# Dental_Sensor.net
KiCad netlist of a schematic drawn in Altium Designer
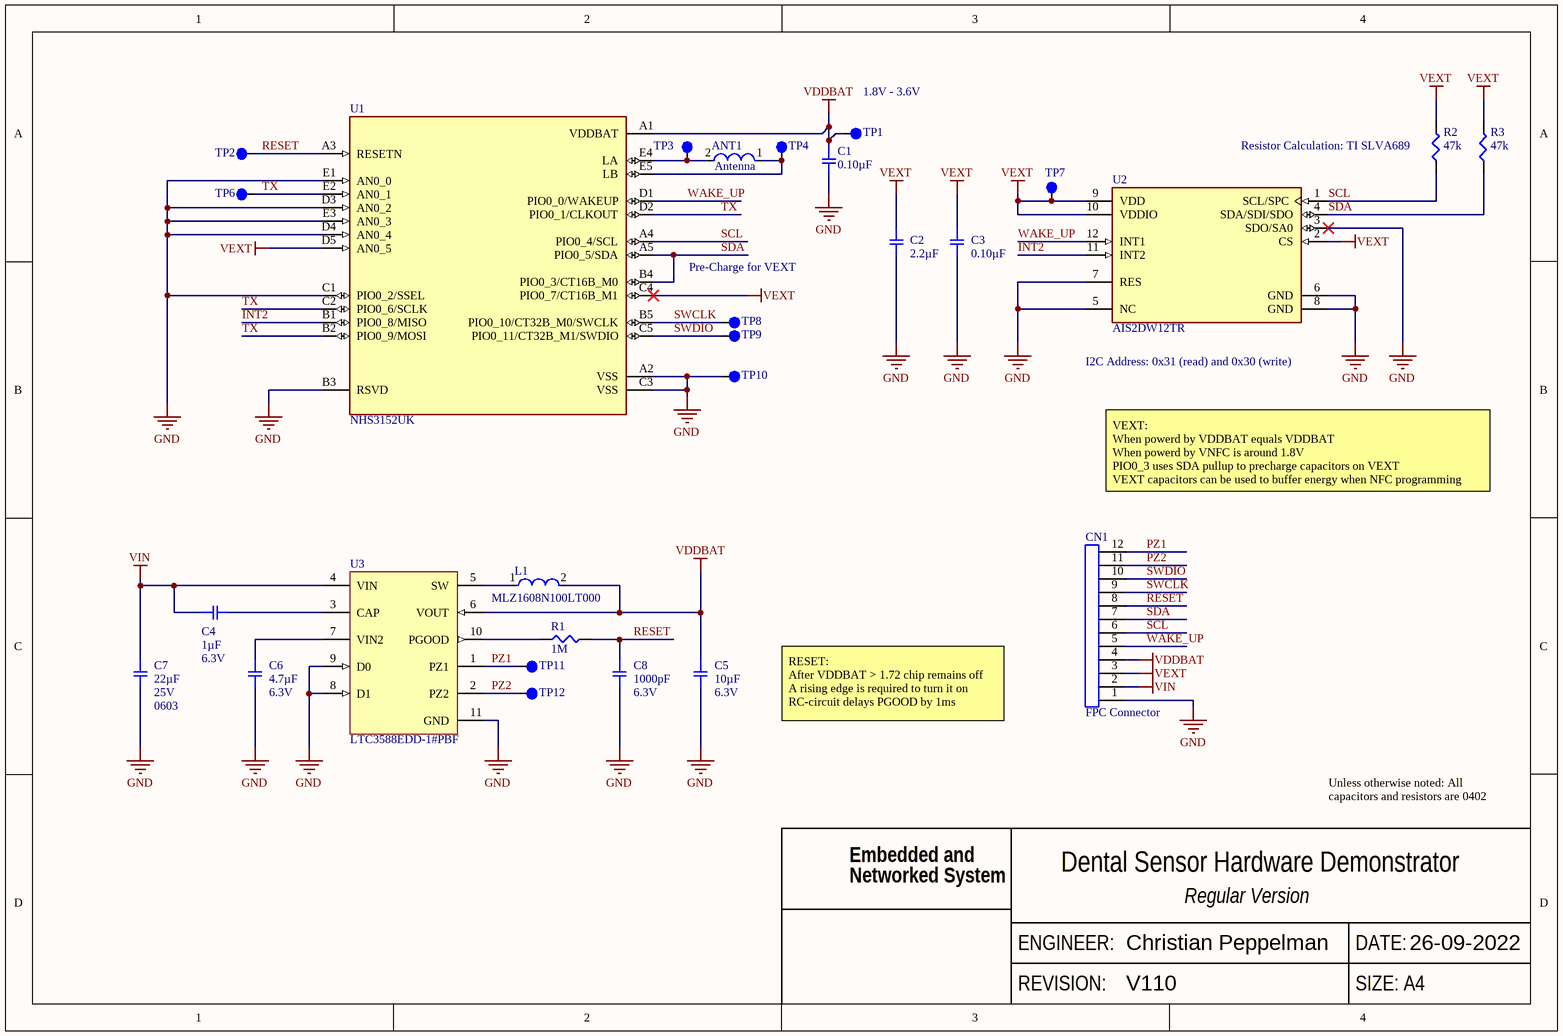
[diagram p0: Dental Sensor.SchDoc]

(export (version "E")
  (design (tool "Eeschema 10.0.6"))
  (components
    (comp (ref "ANT1")
      (value "Antenna")
      (footprint "NFC Antenna")
      (description "Track 0.2; Gap 0.1; Height 4.6; Width 14.5;")
      (libsource (lib "Library") (part "NFC Antenna"))
    )
    (comp (ref "C1")
      (value "0.10µF")
      (footprint "CAPC1005X03N")
      (description "CAP CER 0.1UF 6.3V X5R 0402")
      (fields
        (field (name "DIGI-KEY PART NUMBER") "490-6287-1-ND")
        (field (name "PART NUMBER") "GRM155R60J104KA01D")
      )
      (libsource (lib "capacitor_murata_0402") (part "GRM155R60J104KA01D"))
    )
    (comp (ref "C2")
      (value "2.2µF")
      (footprint "CAPC1005X03N")
      (description "CAP CER 2.2UF 6.3V X5R 0402")
      (fields
        (field (name "DIGI-KEY PART NUMBER") "490-12250-1-ND")
        (field (name "PART NUMBER") "GRT155R60J225KE01D")
      )
      (libsource (lib "capacitor_murata_0402") (part "GRT155R60J225KE01D"))
    )
    (comp (ref "C3")
      (value "0.10µF")
      (footprint "CAPC1005X03N")
      (description "CAP CER 0.1UF 6.3V X5R 0402")
      (fields
        (field (name "DIGI-KEY PART NUMBER") "490-6287-1-ND")
        (field (name "PART NUMBER") "GRM155R60J104KA01D")
      )
      (libsource (lib "capacitor_murata_0402") (part "GRM155R60J104KA01D"))
    )
    (comp (ref "C4")
      (value "1µF")
      (footprint "CAPC1005X03N")
      (description "CAP CER 1UF 6.3V X7R 0402")
      (fields
        (field (name "DIGI-KEY PART NUMBER") "490-9665-1-ND")
        (field (name "PART NUMBER") "GRM155R70J105MA12D")
        (field (name "VOLTAGE") "6.3V")
      )
      (libsource (lib "capacitor_murata_0402") (part "GRM155R70J105MA12D"))
    )
    (comp (ref "C5")
      (value "10µF")
      (footprint "CAPC1005X03N")
      (description "CAP CER 10UF 6.3V X5R 0402")
      (fields
        (field (name "DIGI-KEY PART NUMBER") "490-13811-1-ND")
        (field (name "PART NUMBER") "GRM155R60J106ME44D")
        (field (name "VOLTAGE") "6.3V")
      )
      (libsource (lib "capacitor_murata_0402") (part "GRM155R60J106ME44D"))
    )
    (comp (ref "C6")
      (value "4.7µF")
      (footprint "CAPC1005X03N")
      (description "CAP CER 4.7UF 6.3V X5R 0402")
      (fields
        (field (name "DIGI-KEY PART NUMBER") "490-10983-1-ND")
        (field (name "PART NUMBER") "ZRB15XR60J475ME01D")
        (field (name "VOLTAGE") "6.3V")
      )
      (libsource (lib "capacitor_murata_0402") (part "ZRB15XR60J475ME01D"))
    )
    (comp (ref "C7")
      (value "22µF")
      (footprint "CAPC1608X12N")
      (description "CAP CER 22UF 10V X5R 0603")
      (fields
        (field (name "DIGI-KEY PART NUMBER") "490-13243-1-ND")
        (field (name "PART NUMBER") "GRM187R61A226ME15D")
        (field (name "VOLTAGE") "25V")
        (field (name "PACKAGE / CASE") "0603")
      )
      (libsource (lib "capacitor_murata_0603") (part "GRM187R61A226ME15D"))
    )
    (comp (ref "C8")
      (value "1000pF")
      (footprint "CAPC1005X03N")
      (description "CAP CER 1000PF 6.3V X5R 0402")
      (fields
        (field (name "DIGI-KEY PART NUMBER") "490-6285-1-ND")
        (field (name "PART NUMBER") "GRM155R60J102KA01D")
        (field (name "VOLTAGE") "6.3V")
      )
      (libsource (lib "capacitor_murata_0402") (part "GRM155R60J102KA01D"))
    )
    (comp (ref "CN1")
      (value "FPC Connector")
      (footprint "52745-1297")
      (description "FFC / FPC Board Connector, 0.5 mm, 12 Contacts, Receptacle, Easy-On 52745, Surface Mount, Top")
      (libsource (lib "Library") (part "52745-1297"))
    )
    (comp (ref "L1")
      (value "MLZ1608N100LT000")
      (footprint "FP-MLZ1608-MFG")
      (description "Shielded Multilayer Inductor 10uH ±20% 300mA 780mΩ SMD 0603")
      (fields (field (name "TOLERANCE") "20%"))
      (libsource (lib "Altium Content Vault") (part "725321dda6339637d4d059423bc1c3c"))
    )
    (comp (ref "R1")
      (value "1M")
      (footprint "RESC1005X03N")
      (description "RES SMD 1M OHM 1% 1/10W 0402")
      (fields
        (field (name "PART NUMBER") "ERJ-2RKF1004X")
        (field (name "DIGI-KEY PART NUMBER") "P1.00MLCT-ND")
      )
      (libsource (lib "Panasonic_ERJ_0402") (part "ERJ-2RKF1004X"))
    )
    (comp (ref "R2")
      (value "47k")
      (footprint "RESC1005X03N")
      (description "RES SMD 47K OHM 1% 1/10W 0402")
      (fields
        (field (name "PART NUMBER") "ERJ-2RKF4702X")
        (field (name "DIGI-KEY PART NUMBER") "P47.0KLCT-ND")
      )
      (libsource (lib "Panasonic_ERJ_0402") (part "ERJ-2RKF4702X"))
    )
    (comp (ref "R3")
      (value "47k")
      (footprint "RESC1005X03N")
      (description "RES SMD 47K OHM 1% 1/10W 0402")
      (fields
        (field (name "PART NUMBER") "ERJ-2RKF4702X")
        (field (name "DIGI-KEY PART NUMBER") "P47.0KLCT-ND")
      )
      (libsource (lib "Panasonic_ERJ_0402") (part "ERJ-2RKF4702X"))
    )
    (comp (ref "TP1")
      (value "Testpoint")
      (footprint "Testpoint 0.35mm")
      (libsource (lib "Library") (part "Testpoint"))
    )
    (comp (ref "TP2")
      (value "Testpoint")
      (footprint "Testpoint 0.35mm")
      (libsource (lib "Library") (part "Testpoint"))
    )
    (comp (ref "TP3")
      (value "Testpoint")
      (footprint "Testpoint 0.35mm")
      (libsource (lib "Library") (part "Testpoint"))
    )
    (comp (ref "TP4")
      (value "Testpoint")
      (footprint "Testpoint 0.35mm")
      (libsource (lib "Library") (part "Testpoint"))
    )
    (comp (ref "TP6")
      (value "Testpoint")
      (footprint "Testpoint 0.35mm")
      (libsource (lib "Library") (part "Testpoint"))
    )
    (comp (ref "TP7")
      (value "Testpoint")
      (footprint "Testpoint 0.35mm")
      (libsource (lib "Library") (part "Testpoint"))
    )
    (comp (ref "TP8")
      (value "Testpoint")
      (footprint "Testpoint 0.35mm")
      (libsource (lib "Library") (part "Testpoint"))
    )
    (comp (ref "TP9")
      (value "Testpoint")
      (footprint "Testpoint 0.35mm")
      (libsource (lib "Library") (part "Testpoint"))
    )
    (comp (ref "TP10")
      (value "Testpoint")
      (footprint "Testpoint 0.35mm")
      (libsource (lib "Library") (part "Testpoint"))
    )
    (comp (ref "TP11")
      (value "Testpoint")
      (footprint "Testpoint 0.35mm")
      (libsource (lib "Library") (part "Testpoint"))
    )
    (comp (ref "TP12")
      (value "Testpoint")
      (footprint "Testpoint 0.35mm")
      (libsource (lib "Library") (part "Testpoint"))
    )
    (comp (ref "U1")
      (value "NHS3152UK")
      (footprint "WLCSP25")
      (description "ARM-microcontrollers - MCU NTAG NHS3152 NFC")
      (libsource (lib "Library") (part "NHS3152UK"))
    )
    (comp (ref "U2")
      (value "AIS2DW12TR")
      (footprint "FP-LGA12-DM00369449-MFG")
      (description "MEMS DIGITAL OUTPUT MOTION SENSO")
      (libsource (lib "Altium Content Vault") (part "7c84b71c388d4f21c3e092307226021"))
    )
    (comp (ref "U3")
      (value "LTC3588EDD-1#PBF")
      (footprint "LT-DD-10_V")
      (description "Piezoelectric Energy Harvesting Power Supply, 10-pin SON (DD-10), -40 to 125 degC, Pb-Free")
      (fields (field (name "MANUFACTURER") "Linear Technology"))
      (libsource (lib "Altium Content Vault") (part "LT-LTC3588-DD-10"))
    )
  )
  (nets
    (net (code "1") (name "/INT2") (class "Default")
      (node (ref "U1") (pin "B1") (pinfunction "PIO0_8/MISO_B1") (pintype "bidirectional"))
      (node (ref "U2") (pin "11") (pinfunction "INT2_11") (pintype "input"))
    )
    (net (code "2") (name "/PZ1") (class "Default")
      (node (ref "CN1") (pin "12") (pintype "passive"))
      (node (ref "TP11") (pin "1") (pinfunction "2_1") (pintype "passive"))
      (node (ref "U3") (pin "1") (pinfunction "PZ1_1") (pintype "power_in"))
    )
    (net (code "3") (name "/PZ2") (class "Default")
      (node (ref "CN1") (pin "11") (pintype "passive"))
      (node (ref "TP12") (pin "1") (pinfunction "2_1") (pintype "passive"))
      (node (ref "U3") (pin "2") (pinfunction "PZ2_2") (pintype "power_in"))
    )
    (net (code "4") (name "/RESET") (class "Default")
      (node (ref "C8") (pin "1") (pinfunction "1_1") (pintype "passive"))
      (node (ref "CN1") (pin "8") (pintype "passive"))
      (node (ref "R1") (pin "2") (pinfunction "2_2") (pintype "passive"))
      (node (ref "TP2") (pin "1") (pinfunction "2_1") (pintype "passive"))
      (node (ref "U1") (pin "A3") (pinfunction "RESETN_A3") (pintype "input"))
    )
    (net (code "5") (name "/SCL") (class "Default")
      (node (ref "CN1") (pin "6") (pintype "passive"))
      (node (ref "R2") (pin "1") (pinfunction "1_1") (pintype "passive"))
      (node (ref "U1") (pin "A4") (pinfunction "PIO0_4/SCL_A4") (pintype "bidirectional"))
      (node (ref "U2") (pin "1") (pinfunction "SCL/SPC_1") (pintype "input"))
    )
    (net (code "6") (name "/SDA") (class "Default")
      (node (ref "CN1") (pin "7") (pintype "passive"))
      (node (ref "R3") (pin "1") (pinfunction "1_1") (pintype "passive"))
      (node (ref "U1") (pin "A5") (pinfunction "PIO0_5/SDA_A5") (pintype "bidirectional"))
      (node (ref "U1") (pin "B4") (pinfunction "PIO0_3/CT16B_M0_B4") (pintype "bidirectional"))
      (node (ref "U2") (pin "4") (pinfunction "SDA/SDI/SDO_4") (pintype "bidirectional"))
    )
    (net (code "7") (name "/SWCLK") (class "Default")
      (node (ref "CN1") (pin "9") (pintype "passive"))
      (node (ref "TP8") (pin "1") (pinfunction "2_1") (pintype "passive"))
      (node (ref "U1") (pin "B5") (pinfunction "PIO0_10/CT32B_M0/SWCLK_B5") (pintype "bidirectional"))
    )
    (net (code "8") (name "/SWDIO") (class "Default")
      (node (ref "CN1") (pin "10") (pintype "passive"))
      (node (ref "TP9") (pin "1") (pinfunction "2_1") (pintype "passive"))
      (node (ref "U1") (pin "C5") (pinfunction "PIO0_11/CT32B_M1/SWDIO_C5") (pintype "bidirectional"))
    )
    (net (code "9") (name "/TX") (class "Default")
      (node (ref "TP6") (pin "1") (pinfunction "2_1") (pintype "passive"))
      (node (ref "U1") (pin "B2") (pinfunction "PIO0_9/MOSI_B2") (pintype "bidirectional"))
      (node (ref "U1") (pin "C2") (pinfunction "PIO0_6/SCLK_C2") (pintype "bidirectional"))
      (node (ref "U1") (pin "D2") (pinfunction "PIO0_1/CLKOUT_D2") (pintype "bidirectional"))
      (node (ref "U1") (pin "E2") (pinfunction "AN0_1_E2") (pintype "input"))
    )
    (net (code "10") (name "/WAKE_UP") (class "Default")
      (node (ref "CN1") (pin "5") (pintype "passive"))
      (node (ref "U1") (pin "D1") (pinfunction "PIO0_0/WAKEUP_D1") (pintype "bidirectional"))
      (node (ref "U2") (pin "12") (pinfunction "INT1_12") (pintype "input"))
    )
    (net (code "11") (name "GND") (class "Default")
      (node (ref "C1") (pin "2") (pinfunction "2_2") (pintype "passive"))
      (node (ref "C2") (pin "2") (pinfunction "2_2") (pintype "passive"))
      (node (ref "C3") (pin "2") (pinfunction "2_2") (pintype "passive"))
      (node (ref "C5") (pin "2") (pinfunction "2_2") (pintype "passive"))
      (node (ref "C6") (pin "2") (pinfunction "2_2") (pintype "passive"))
      (node (ref "C7") (pin "2") (pinfunction "2_2") (pintype "passive"))
      (node (ref "C8") (pin "2") (pinfunction "2_2") (pintype "passive"))
      (node (ref "CN1") (pin "1") (pintype "passive"))
      (node (ref "TP10") (pin "1") (pinfunction "2_1") (pintype "passive"))
      (node (ref "U1") (pin "A2") (pinfunction "VSS_A2") (pintype "power_in"))
      (node (ref "U1") (pin "B3") (pinfunction "RSVD_B3") (pintype "passive"))
      (node (ref "U1") (pin "C1") (pinfunction "PIO0_2/SSEL_C1") (pintype "bidirectional"))
      (node (ref "U1") (pin "C3") (pinfunction "VSS_C3") (pintype "power_in"))
      (node (ref "U1") (pin "D3") (pinfunction "AN0_2_D3") (pintype "input"))
      (node (ref "U1") (pin "D4") (pinfunction "AN0_4_D4") (pintype "input"))
      (node (ref "U1") (pin "E1") (pinfunction "AN0_0_E1") (pintype "input"))
      (node (ref "U1") (pin "E3") (pinfunction "AN0_3_E3") (pintype "input"))
      (node (ref "U2") (pin "3") (pinfunction "SDO/SA0_3") (pintype "bidirectional"))
      (node (ref "U2") (pin "5") (pinfunction "NC_5") (pintype "passive"))
      (node (ref "U2") (pin "6") (pinfunction "GND_6") (pintype "power_in"))
      (node (ref "U2") (pin "7") (pinfunction "RES_7") (pintype "passive"))
      (node (ref "U2") (pin "8") (pinfunction "GND_8") (pintype "power_in"))
      (node (ref "U3") (pin "11") (pinfunction "GND_11") (pintype "power_in"))
      (node (ref "U3") (pin "8") (pinfunction "D1_8") (pintype "input"))
      (node (ref "U3") (pin "9") (pinfunction "D0_9") (pintype "input"))
    )
    (net (code "12") (name "Net-(TP3-2)") (class "Default")
      (node (ref "ANT1") (pin "2") (pinfunction "2_2") (pintype "passive"))
      (node (ref "TP3") (pin "1") (pinfunction "2_1") (pintype "passive"))
      (node (ref "U1") (pin "E4") (pinfunction "LA_E4") (pintype "bidirectional"))
    )
    (net (code "13") (name "Net-(TP4-2)") (class "Default")
      (node (ref "ANT1") (pin "1") (pinfunction "1_1") (pintype "passive"))
      (node (ref "TP4") (pin "1") (pinfunction "2_1") (pintype "passive"))
      (node (ref "U1") (pin "E5") (pinfunction "LB_E5") (pintype "bidirectional"))
    )
    (net (code "14") (name "Net-(U3-CAP)") (class "Default")
      (node (ref "C4") (pin "2") (pinfunction "2_2") (pintype "passive"))
      (node (ref "U3") (pin "3") (pinfunction "CAP_3") (pintype "passive"))
    )
    (net (code "15") (name "Net-(U3-PGOOD)") (class "Default")
      (node (ref "R1") (pin "1") (pinfunction "1_1") (pintype "passive"))
      (node (ref "U3") (pin "10") (pinfunction "PGOOD_10") (pintype "output"))
    )
    (net (code "16") (name "Net-(U3-SW)") (class "Default")
      (node (ref "L1") (pin "1") (pinfunction "1_1") (pintype "passive"))
      (node (ref "U3") (pin "5") (pinfunction "SW_5") (pintype "power_in"))
    )
    (net (code "17") (name "Net-(U3-VIN2)") (class "Default")
      (node (ref "C6") (pin "1") (pinfunction "1_1") (pintype "passive"))
      (node (ref "U3") (pin "7") (pinfunction "VIN2_7") (pintype "power_in"))
    )
    (net (code "18") (name "VDDBAT") (class "Default")
      (node (ref "C1") (pin "1") (pinfunction "1_1") (pintype "passive"))
      (node (ref "C5") (pin "1") (pinfunction "1_1") (pintype "passive"))
      (node (ref "CN1") (pin "4") (pintype "passive"))
      (node (ref "L1") (pin "2") (pinfunction "2_2") (pintype "passive"))
      (node (ref "TP1") (pin "1") (pinfunction "2_1") (pintype "passive"))
      (node (ref "U1") (pin "A1") (pinfunction "VDDBAT_A1") (pintype "power_in"))
      (node (ref "U3") (pin "6") (pinfunction "VOUT_6") (pintype "input"))
    )
    (net (code "19") (name "VEXT") (class "Default")
      (node (ref "C2") (pin "1") (pinfunction "1_1") (pintype "passive"))
      (node (ref "C3") (pin "1") (pinfunction "1_1") (pintype "passive"))
      (node (ref "CN1") (pin "3") (pintype "passive"))
      (node (ref "R2") (pin "2") (pinfunction "2_2") (pintype "passive"))
      (node (ref "R3") (pin "2") (pinfunction "2_2") (pintype "passive"))
      (node (ref "TP7") (pin "1") (pinfunction "2_1") (pintype "passive"))
      (node (ref "U1") (pin "C4") (pinfunction "PIO0_7/CT16B_M1_C4") (pintype "bidirectional"))
      (node (ref "U1") (pin "D5") (pinfunction "AN0_5_D5") (pintype "input"))
      (node (ref "U2") (pin "10") (pinfunction "VDDIO_10") (pintype "power_in"))
      (node (ref "U2") (pin "2") (pinfunction "CS_2") (pintype "input"))
      (node (ref "U2") (pin "9") (pinfunction "VDD_9") (pintype "power_in"))
    )
    (net (code "20") (name "VIN") (class "Default")
      (node (ref "C4") (pin "1") (pinfunction "1_1") (pintype "passive"))
      (node (ref "C7") (pin "1") (pinfunction "1_1") (pintype "passive"))
      (node (ref "CN1") (pin "2") (pintype "passive"))
      (node (ref "U3") (pin "4") (pinfunction "VIN_4") (pintype "power_in"))
    )
  )
)
